# schematic.net
KiCad netlist of a schematic drawn in EAGLE
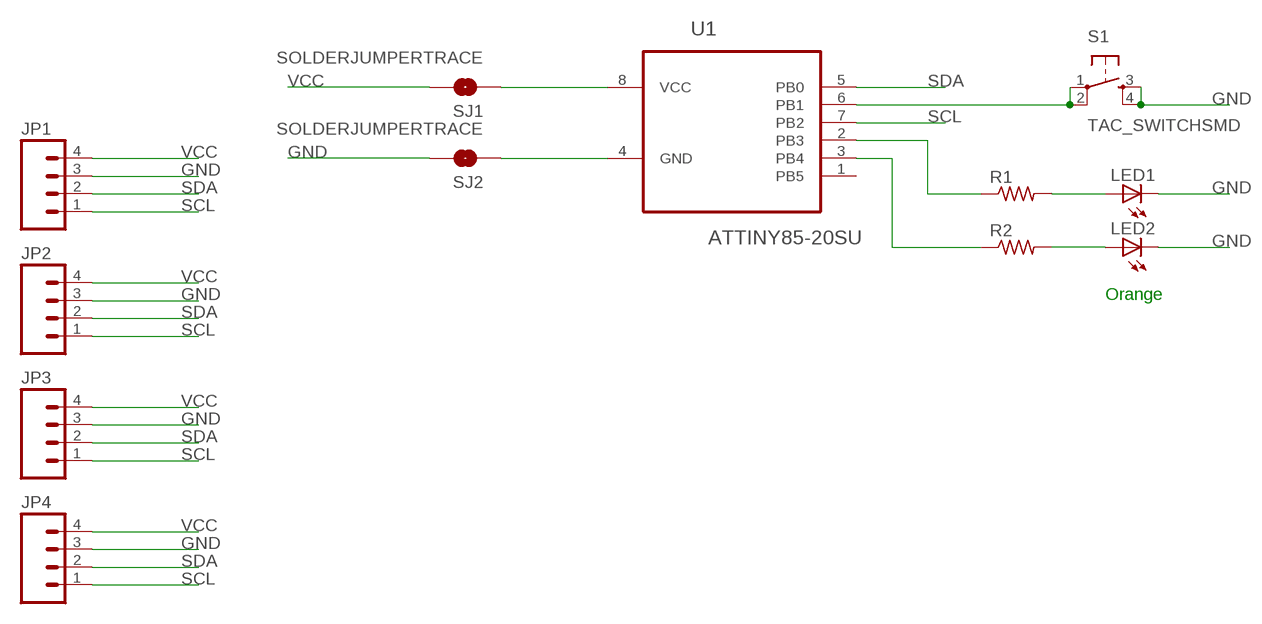
[diagram p0: schematic, sheet 1]

(export (version "E")
  (design (tool "Eeschema 10.0.6"))
  (components
    (comp (ref "JP1")
      (value "M041X04_NO_SILK")
      (footprint "eagle-import:1X04_NO_SILK")
      (libsource (lib "eagle-import") (part "M041X04_NO_SILK"))
    )
    (comp (ref "JP2")
      (value "M041X04_NO_SILK")
      (footprint "eagle-import:1X04_NO_SILK")
      (libsource (lib "eagle-import") (part "M041X04_NO_SILK"))
    )
    (comp (ref "JP3")
      (value "M041X04_NO_SILK")
      (footprint "eagle-import:1X04_NO_SILK")
      (libsource (lib "eagle-import") (part "M041X04_NO_SILK"))
    )
    (comp (ref "JP4")
      (value "M041X04_NO_SILK")
      (footprint "eagle-import:1X04_NO_SILK")
      (libsource (lib "eagle-import") (part "M041X04_NO_SILK"))
    )
    (comp (ref "LED1")
      (value "LEDCHIP-LED0805")
      (footprint "eagle-import:CHIP-LED0805")
      (libsource (lib "eagle-import") (part "LEDCHIP-LED0805"))
    )
    (comp (ref "LED2")
      (value "LEDCHIP-LED0805")
      (footprint "eagle-import:CHIP-LED0805")
      (libsource (lib "eagle-import") (part "LEDCHIP-LED0805"))
    )
    (comp (ref "R1")
      (value "R-US_R0805")
      (footprint "eagle-import:R0805")
      (libsource (lib "eagle-import") (part "R-US_R0805"))
    )
    (comp (ref "R2")
      (value "R-US_R0805")
      (footprint "eagle-import:R0805")
      (libsource (lib "eagle-import") (part "R-US_R0805"))
    )
    (comp (ref "S1")
      (value "TAC_SWITCHSMD")
      (footprint "eagle-import:TACTILE-SWITCH-SMD")
      (libsource (lib "eagle-import") (part "TAC_SWITCHSMD"))
    )
    (comp (ref "SJ1")
      (value "SOLDERJUMPERTRACE")
      (footprint "eagle-import:SJ_2S-TRACE")
      (libsource (lib "eagle-import") (part "SOLDERJUMPERTRACE"))
    )
    (comp (ref "SJ2")
      (value "SOLDERJUMPERTRACE")
      (footprint "eagle-import:SJ_2S-TRACE")
      (libsource (lib "eagle-import") (part "SOLDERJUMPERTRACE"))
    )
    (comp (ref "U1")
      (value "ATTINY85-20SU")
      (footprint "eagle-import:SOIC127P798X216-8N")
      (libsource (lib "eagle-import") (part "ATTINY85-20SU"))
    )
  )
  (nets
    (net (code "1") (name "/GND") (class "Default")
      (node (ref "JP1") (pin "3") (pinfunction "3_3") (pintype "passive"))
      (node (ref "JP2") (pin "3") (pinfunction "3_3") (pintype "passive"))
      (node (ref "JP3") (pin "3") (pinfunction "3_3") (pintype "passive"))
      (node (ref "JP4") (pin "3") (pinfunction "3_3") (pintype "passive"))
      (node (ref "LED1") (pin "C") (pinfunction "C_C") (pintype "passive"))
      (node (ref "LED2") (pin "C") (pinfunction "C_C") (pintype "passive"))
      (node (ref "S1") (pin "3") (pinfunction "3_3") (pintype "passive"))
      (node (ref "S1") (pin "4") (pinfunction "4_4") (pintype "passive"))
      (node (ref "SJ2") (pin "2") (pinfunction "2_2") (pintype "passive"))
    )
    (net (code "2") (name "/SCL") (class "Default")
      (node (ref "JP1") (pin "1") (pinfunction "1_1") (pintype "passive"))
      (node (ref "JP2") (pin "1") (pinfunction "1_1") (pintype "passive"))
      (node (ref "JP3") (pin "1") (pinfunction "1_1") (pintype "passive"))
      (node (ref "JP4") (pin "1") (pinfunction "1_1") (pintype "passive"))
      (node (ref "U1") (pin "7") (pinfunction "PB2_7") (pintype "bidirectional"))
    )
    (net (code "3") (name "/SDA") (class "Default")
      (node (ref "JP1") (pin "2") (pinfunction "2_2") (pintype "passive"))
      (node (ref "JP2") (pin "2") (pinfunction "2_2") (pintype "passive"))
      (node (ref "JP3") (pin "2") (pinfunction "2_2") (pintype "passive"))
      (node (ref "JP4") (pin "2") (pinfunction "2_2") (pintype "passive"))
      (node (ref "U1") (pin "5") (pinfunction "PB0_5") (pintype "bidirectional"))
    )
    (net (code "4") (name "/VCC") (class "Default")
      (node (ref "JP1") (pin "4") (pinfunction "4_4") (pintype "passive"))
      (node (ref "JP2") (pin "4") (pinfunction "4_4") (pintype "passive"))
      (node (ref "JP3") (pin "4") (pinfunction "4_4") (pintype "passive"))
      (node (ref "JP4") (pin "4") (pinfunction "4_4") (pintype "passive"))
      (node (ref "SJ1") (pin "2") (pinfunction "2_2") (pintype "passive"))
    )
    (net (code "5") (name "Net-(LED1-PadA)") (class "Default")
      (node (ref "LED1") (pin "A") (pinfunction "A_A") (pintype "passive"))
      (node (ref "R1") (pin "2") (pinfunction "2_2") (pintype "passive"))
    )
    (net (code "6") (name "Net-(LED2-PadA)") (class "Default")
      (node (ref "LED2") (pin "A") (pinfunction "A_A") (pintype "passive"))
      (node (ref "R2") (pin "2") (pinfunction "2_2") (pintype "passive"))
    )
    (net (code "7") (name "Net-(U1-GND)") (class "Default")
      (node (ref "SJ2") (pin "1") (pinfunction "1_1") (pintype "passive"))
      (node (ref "U1") (pin "4") (pinfunction "GND_4") (pintype "passive"))
    )
    (net (code "8") (name "Net-(U1-PB1)") (class "Default")
      (node (ref "S1") (pin "1") (pinfunction "1_1") (pintype "passive"))
      (node (ref "S1") (pin "2") (pinfunction "2_2") (pintype "passive"))
      (node (ref "U1") (pin "6") (pinfunction "PB1_6") (pintype "bidirectional"))
    )
    (net (code "9") (name "Net-(U1-PB3)") (class "Default")
      (node (ref "R1") (pin "1") (pinfunction "1_1") (pintype "passive"))
      (node (ref "U1") (pin "2") (pinfunction "PB3_2") (pintype "bidirectional"))
    )
    (net (code "10") (name "Net-(U1-PB4)") (class "Default")
      (node (ref "R2") (pin "1") (pinfunction "1_1") (pintype "passive"))
      (node (ref "U1") (pin "3") (pinfunction "PB4_3") (pintype "bidirectional"))
    )
    (net (code "11") (name "Net-(U1-VCC)") (class "Default")
      (node (ref "SJ1") (pin "1") (pinfunction "1_1") (pintype "passive"))
      (node (ref "U1") (pin "8") (pinfunction "VCC_8") (pintype "power_in"))
    )
    (net (code "12") (name "unconnected-(U1-PB5-Pad1)") (class "Default")
      (node (ref "U1") (pin "1") (pinfunction "PB5_1") (pintype "bidirectional"))
    )
  )
)
